# Power_Amp_V3_0.net
KiCad netlist of a schematic drawn in EAGLE
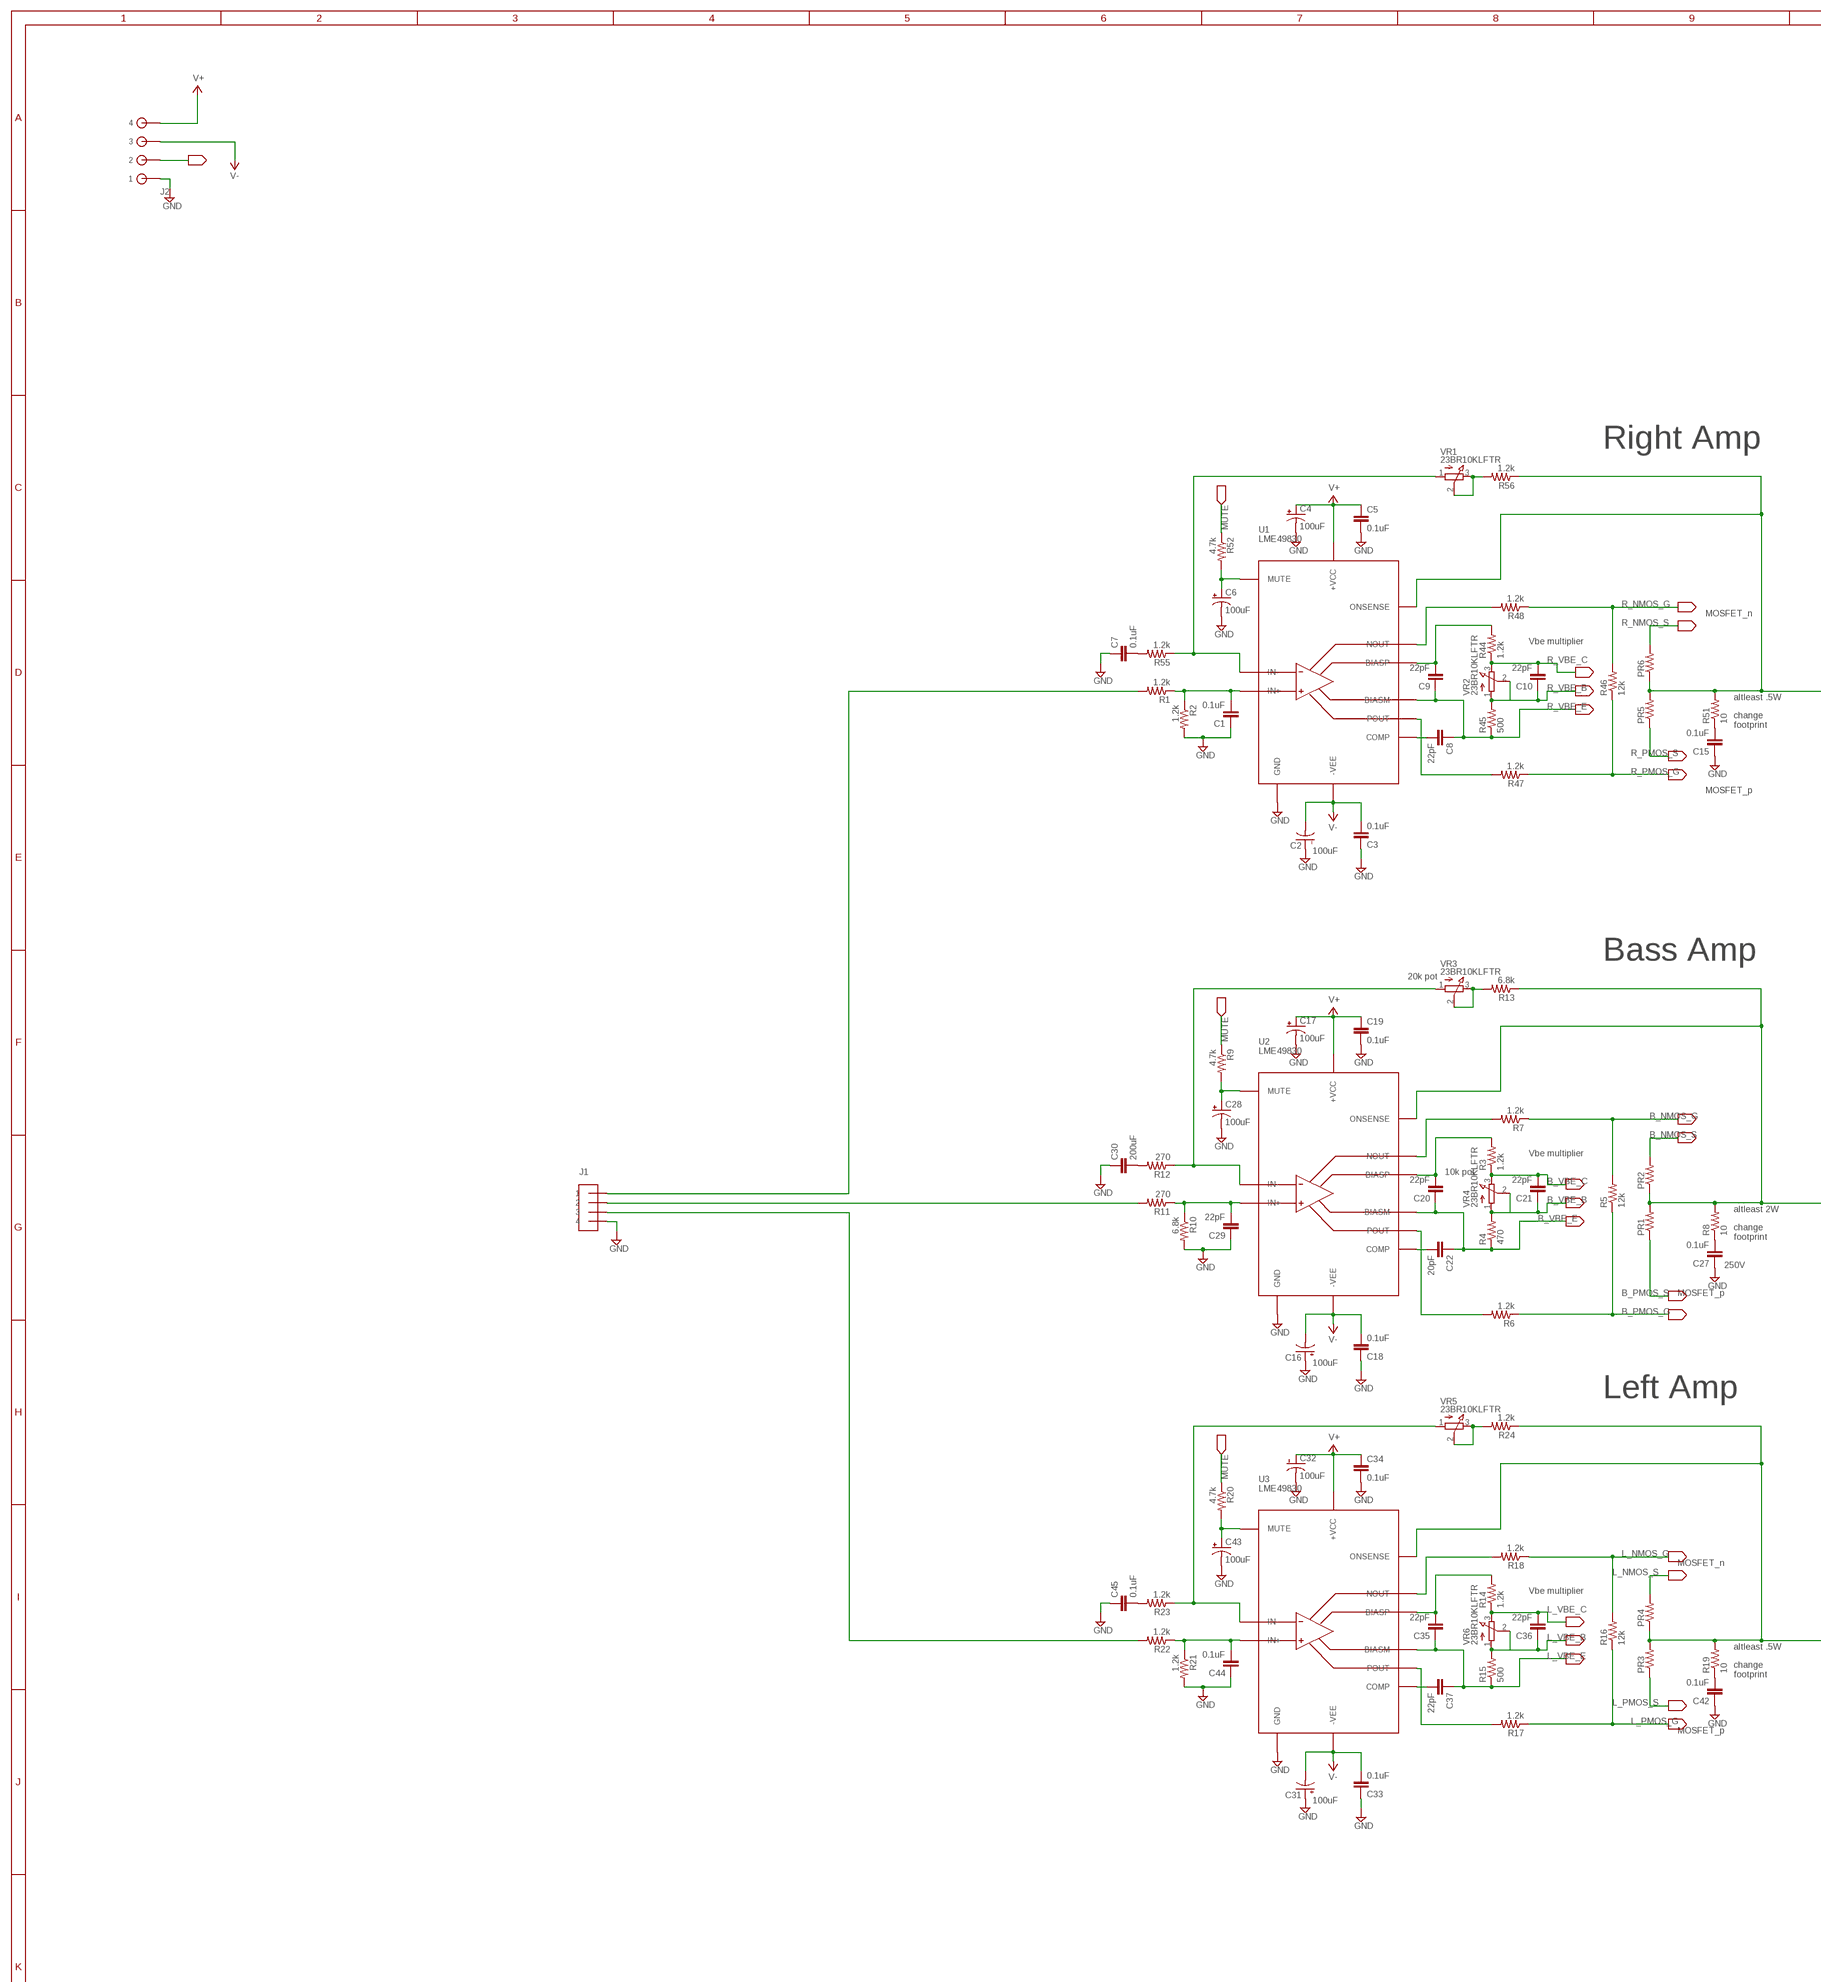
[diagram p0: schematic, sheet 1, part 1 of 3]
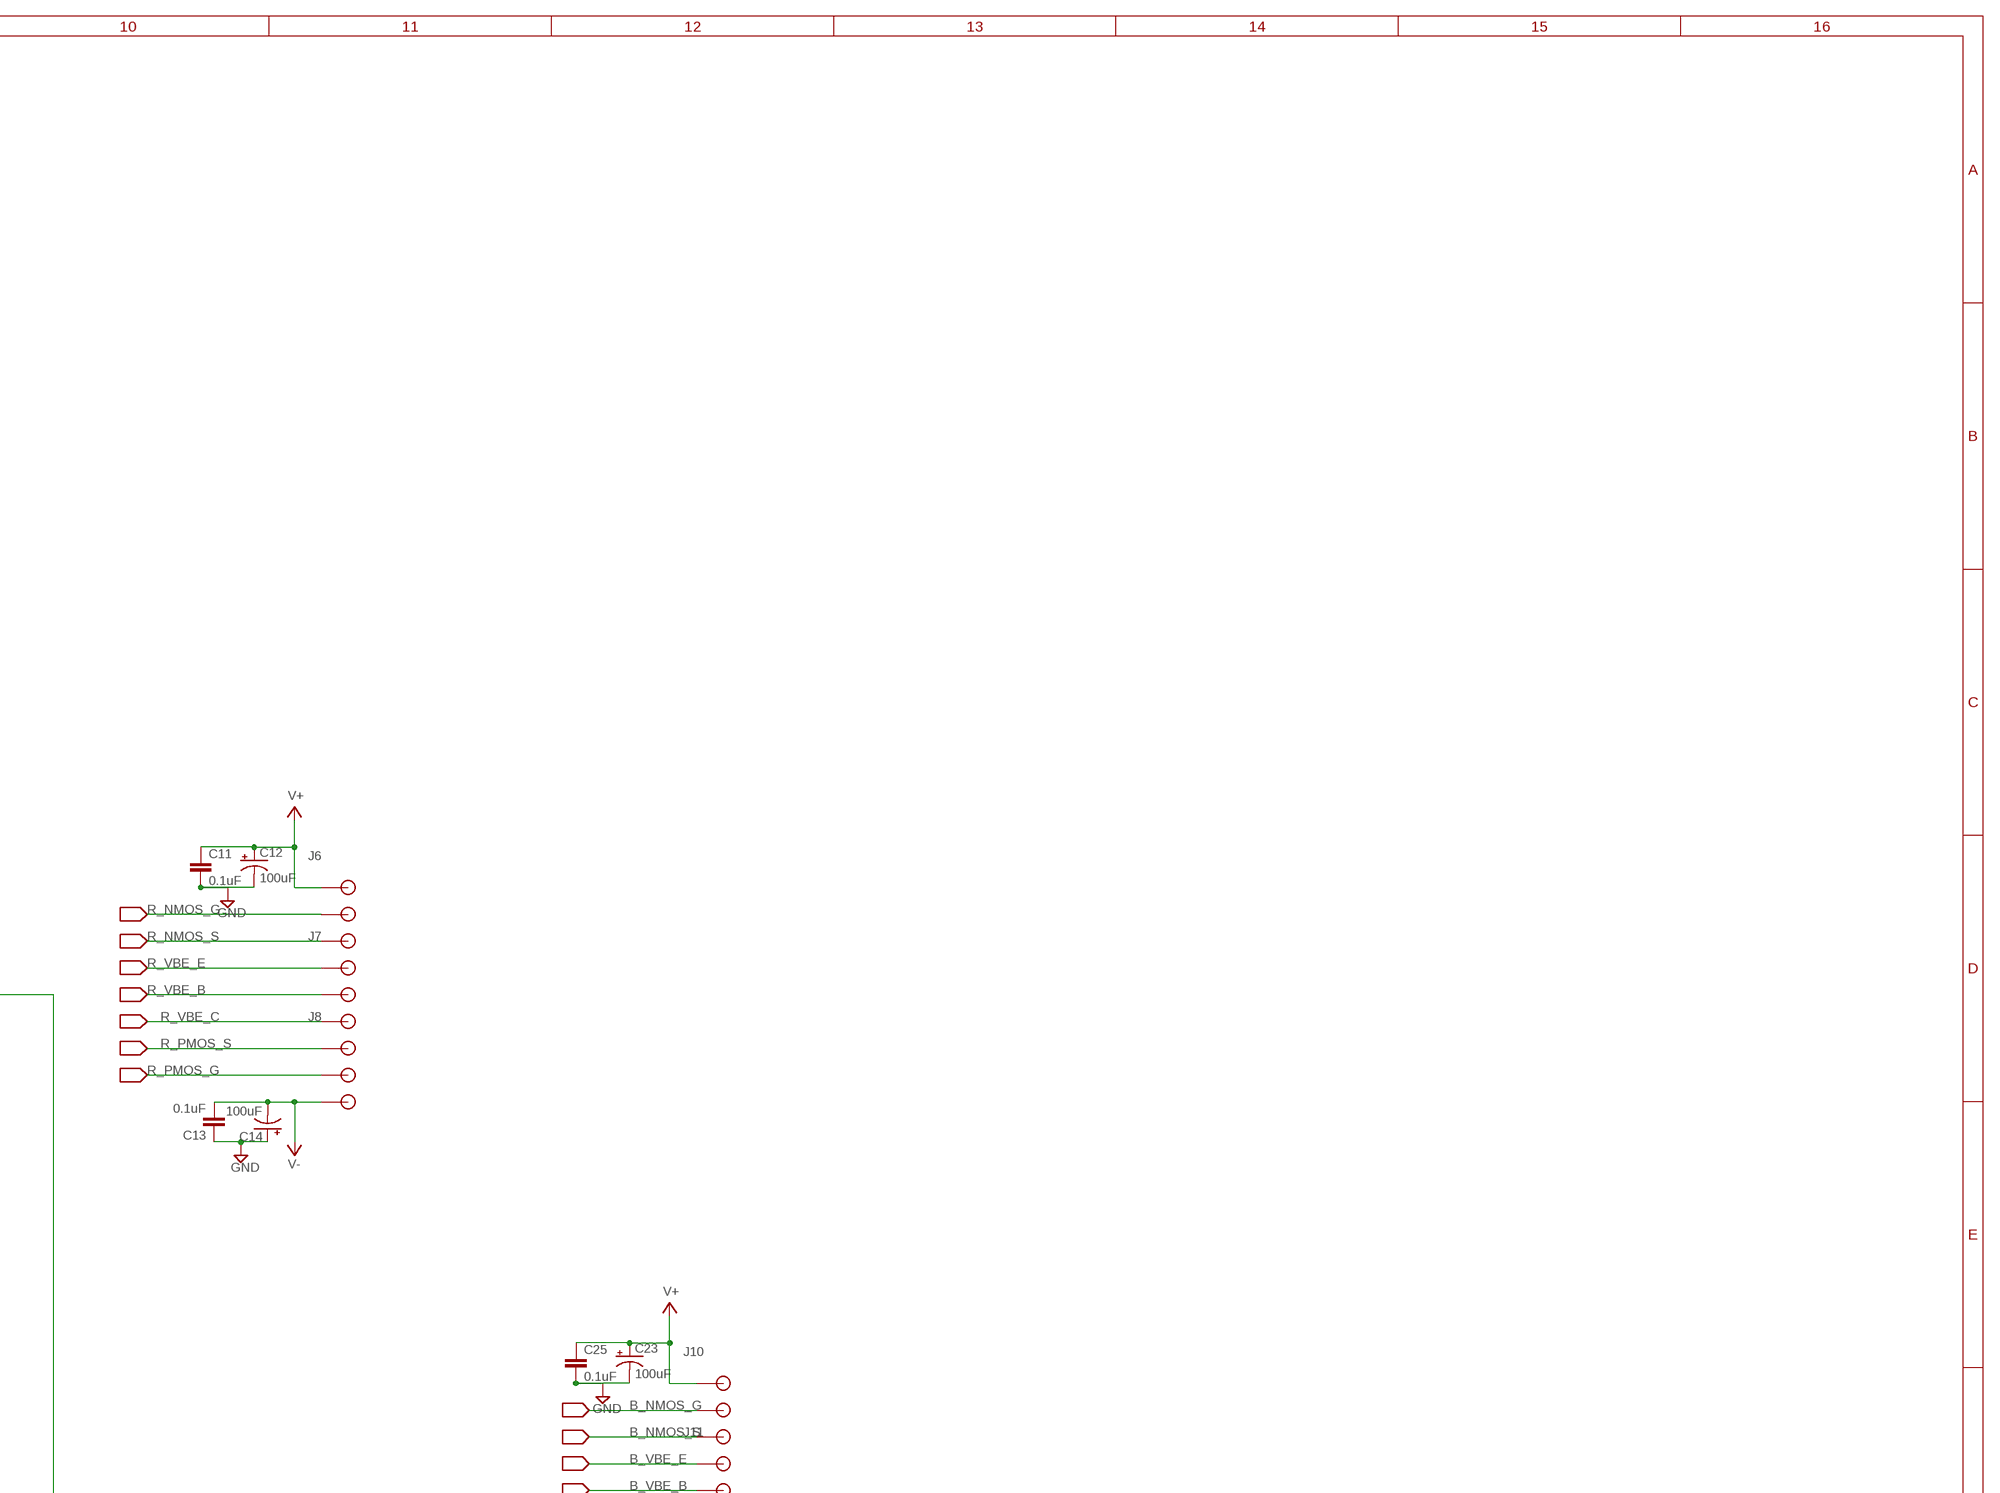
[diagram p1: schematic, sheet 1, part 2 of 3]
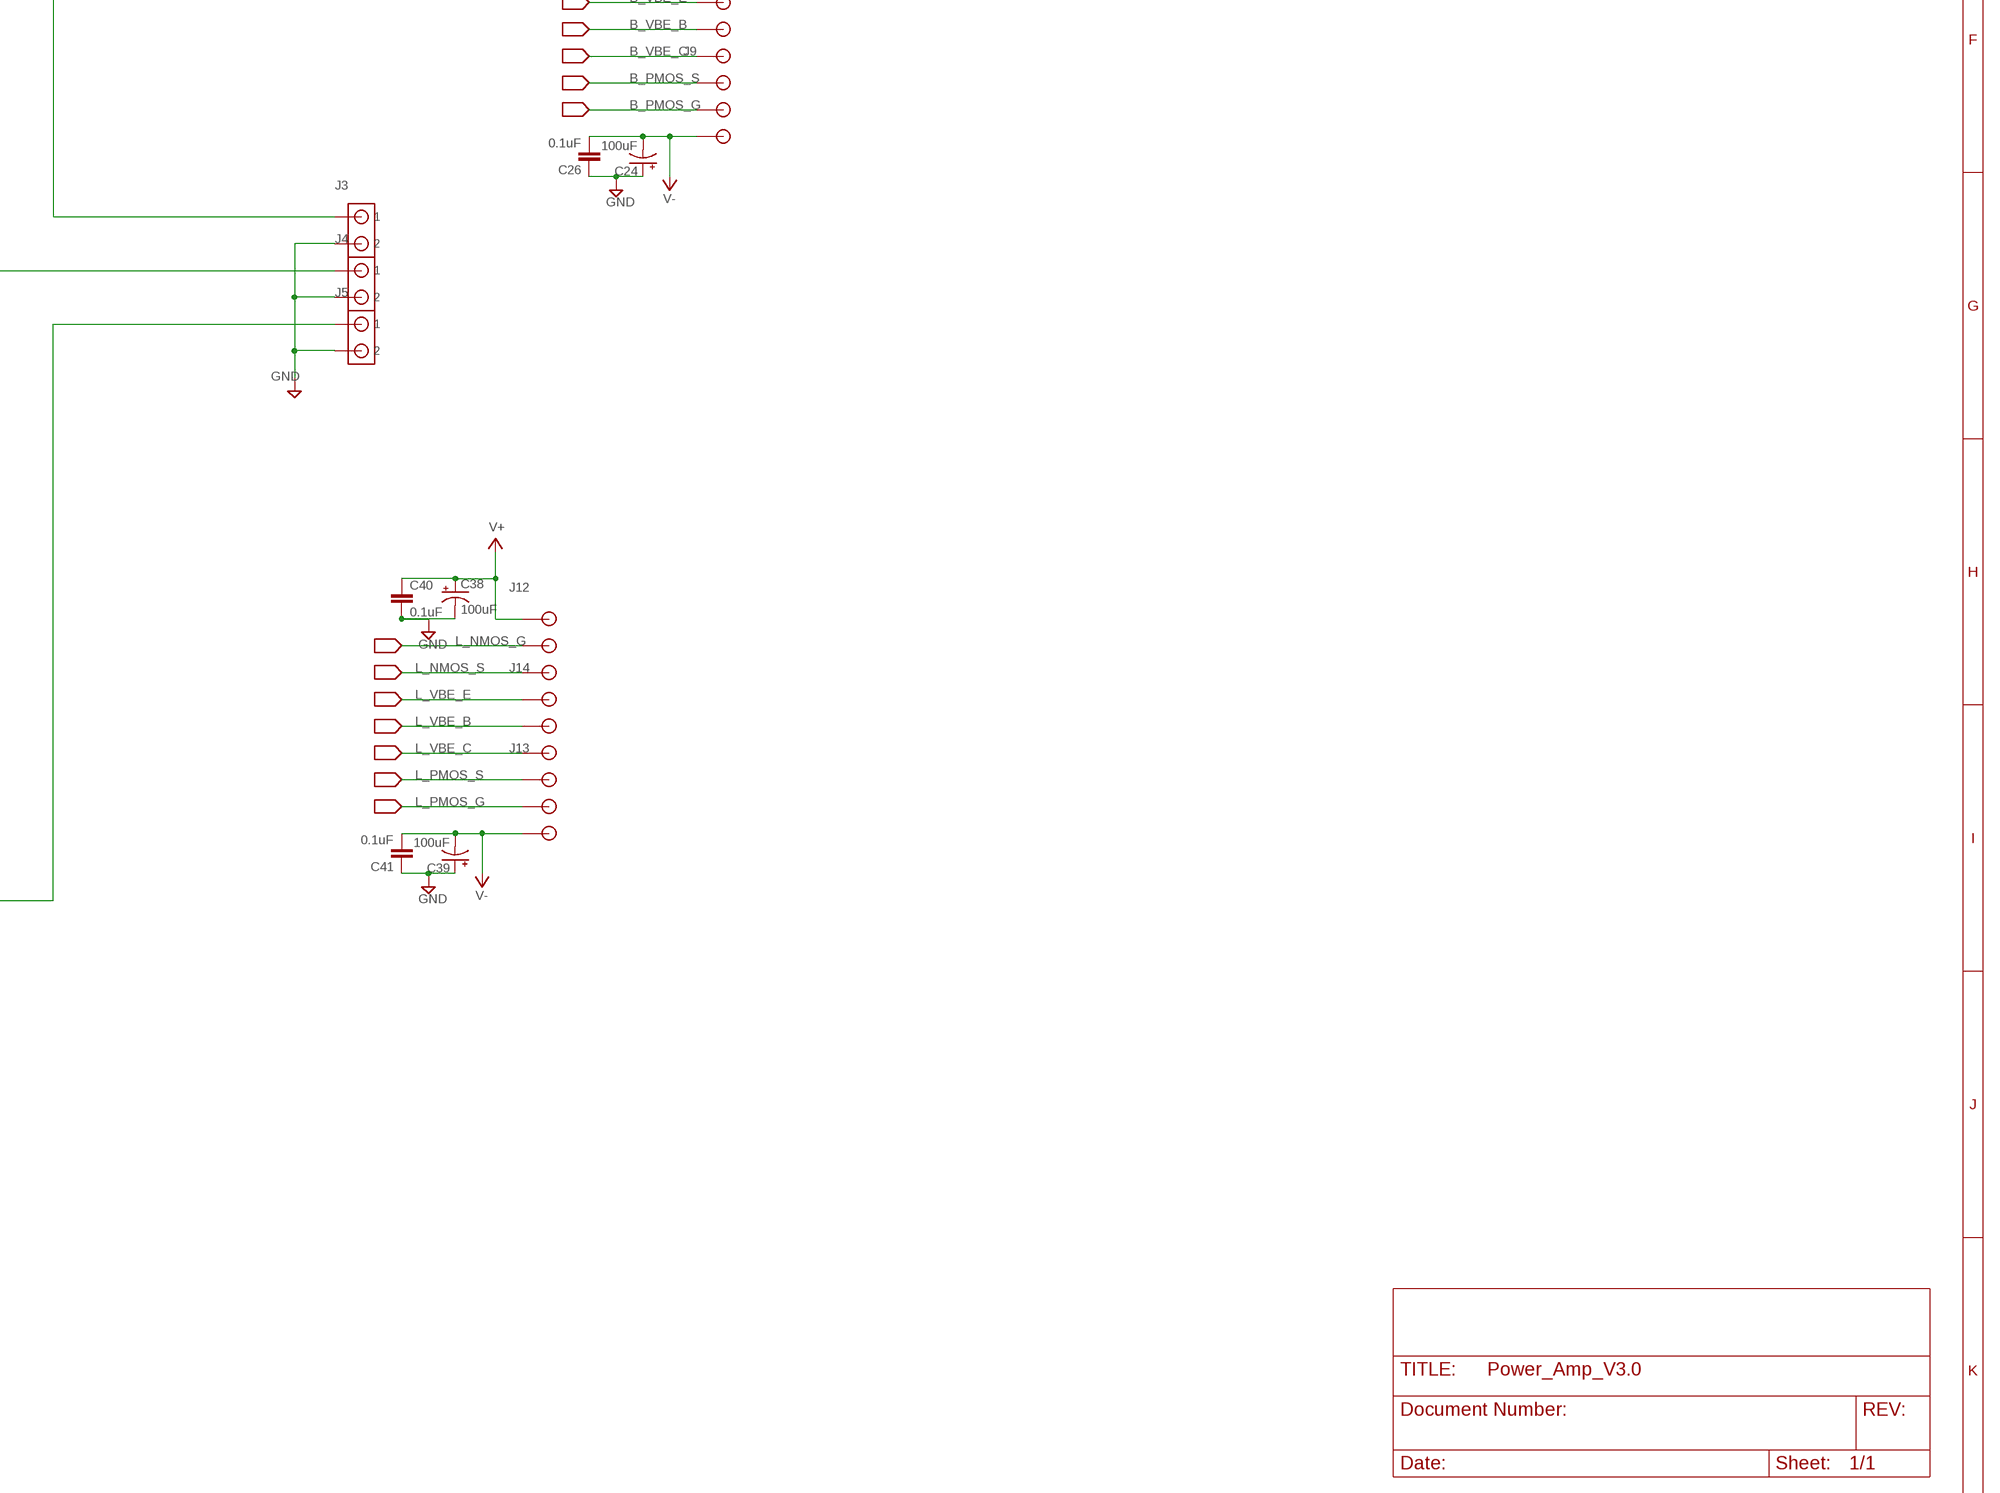
[diagram p2: schematic, sheet 1, part 3 of 3]

(export (version "E")
  (design (tool "Eeschema 10.0.6"))
  (components
    (comp (ref "C1")
      (value "0.1uF")
      (footprint "eagle-import:C050-024X044")
      (libsource (lib "eagle-import") (part "C-EU050-024X044"))
    )
    (comp (ref "C2")
      (value "100uF")
      (footprint "eagle-import:E2,5-6")
      (libsource (lib "eagle-import") (part "CPOL-USE2.5-6"))
    )
    (comp (ref "C3")
      (value "0.1uF")
      (footprint "eagle-import:C050-024X044")
      (libsource (lib "eagle-import") (part "C-EU050-024X044"))
    )
    (comp (ref "C4")
      (value "100uF")
      (footprint "eagle-import:E2,5-6")
      (libsource (lib "eagle-import") (part "CPOL-USE2.5-6"))
    )
    (comp (ref "C5")
      (value "0.1uF")
      (footprint "eagle-import:C050-024X044")
      (libsource (lib "eagle-import") (part "C-EU050-024X044"))
    )
    (comp (ref "C6")
      (value "100uF")
      (footprint "eagle-import:E2,5-6")
      (libsource (lib "eagle-import") (part "CPOL-USE2.5-6"))
    )
    (comp (ref "C7")
      (value "0.1uF")
      (footprint "eagle-import:C050-024X044")
      (libsource (lib "eagle-import") (part "C-EU050-024X044"))
    )
    (comp (ref "C8")
      (value "22pF")
      (footprint "eagle-import:C050-024X044")
      (libsource (lib "eagle-import") (part "C-EU050-024X044"))
    )
    (comp (ref "C9")
      (value "22pF")
      (footprint "eagle-import:C050-024X044")
      (libsource (lib "eagle-import") (part "C-EU050-024X044"))
    )
    (comp (ref "C10")
      (value "22pF")
      (footprint "eagle-import:C050-024X044")
      (libsource (lib "eagle-import") (part "C-EU050-024X044"))
    )
    (comp (ref "C11")
      (value "0.1uF")
      (footprint "eagle-import:C050-024X044")
      (libsource (lib "eagle-import") (part "C-EU050-024X044"))
    )
    (comp (ref "C12")
      (value "100uF")
      (footprint "eagle-import:E2,5-6")
      (libsource (lib "eagle-import") (part "CPOL-USE2.5-6"))
    )
    (comp (ref "C13")
      (value "0.1uF")
      (footprint "eagle-import:C050-024X044")
      (libsource (lib "eagle-import") (part "C-EU050-024X044"))
    )
    (comp (ref "C14")
      (value "100uF")
      (footprint "eagle-import:E2,5-6")
      (libsource (lib "eagle-import") (part "CPOL-USE2.5-6"))
    )
    (comp (ref "C15")
      (value "0.1uF")
      (footprint "eagle-import:C050-024X044")
      (libsource (lib "eagle-import") (part "C-EU050-024X044"))
    )
    (comp (ref "C16")
      (value "100uF")
      (footprint "eagle-import:E2,5-6")
      (libsource (lib "eagle-import") (part "CPOL-USE2.5-6"))
    )
    (comp (ref "C17")
      (value "100uF")
      (footprint "eagle-import:E2,5-6")
      (libsource (lib "eagle-import") (part "CPOL-USE2.5-6"))
    )
    (comp (ref "C18")
      (value "0.1uF")
      (footprint "eagle-import:C050-024X044")
      (libsource (lib "eagle-import") (part "C-EU050-024X044"))
    )
    (comp (ref "C19")
      (value "0.1uF")
      (footprint "eagle-import:C050-024X044")
      (libsource (lib "eagle-import") (part "C-EU050-024X044"))
    )
    (comp (ref "C20")
      (value "22pF")
      (footprint "eagle-import:C050-024X044")
      (libsource (lib "eagle-import") (part "C-EU050-024X044"))
    )
    (comp (ref "C21")
      (value "22pF")
      (footprint "eagle-import:C050-024X044")
      (libsource (lib "eagle-import") (part "C-EU050-024X044"))
    )
    (comp (ref "C22")
      (value "20pF")
      (footprint "eagle-import:C050-024X044")
      (libsource (lib "eagle-import") (part "C-EU050-024X044"))
    )
    (comp (ref "C23")
      (value "100uF")
      (footprint "eagle-import:E2,5-6")
      (libsource (lib "eagle-import") (part "CPOL-USE2.5-6"))
    )
    (comp (ref "C24")
      (value "100uF")
      (footprint "eagle-import:E2,5-6")
      (libsource (lib "eagle-import") (part "CPOL-USE2.5-6"))
    )
    (comp (ref "C25")
      (value "0.1uF")
      (footprint "eagle-import:C050-024X044")
      (libsource (lib "eagle-import") (part "C-EU050-024X044"))
    )
    (comp (ref "C26")
      (value "0.1uF")
      (footprint "eagle-import:C050-024X044")
      (libsource (lib "eagle-import") (part "C-EU050-024X044"))
    )
    (comp (ref "C27")
      (value "0.1uF")
      (footprint "eagle-import:C050-024X044")
      (libsource (lib "eagle-import") (part "C-EU050-024X044"))
    )
    (comp (ref "C28")
      (value "100uF")
      (footprint "eagle-import:E2,5-6")
      (libsource (lib "eagle-import") (part "CPOL-USE2.5-6"))
    )
    (comp (ref "C29")
      (value "22pF")
      (footprint "eagle-import:C050-024X044")
      (libsource (lib "eagle-import") (part "C-EU050-024X044"))
    )
    (comp (ref "C30")
      (value "200uF")
      (footprint "eagle-import:C050-024X044")
      (libsource (lib "eagle-import") (part "C-EU050-024X044"))
    )
    (comp (ref "C31")
      (value "100uF")
      (footprint "eagle-import:E2,5-6")
      (libsource (lib "eagle-import") (part "CPOL-USE2.5-6"))
    )
    (comp (ref "C32")
      (value "100uF")
      (footprint "eagle-import:E2,5-6")
      (libsource (lib "eagle-import") (part "CPOL-USE2.5-6"))
    )
    (comp (ref "C33")
      (value "0.1uF")
      (footprint "eagle-import:C050-024X044")
      (libsource (lib "eagle-import") (part "C-EU050-024X044"))
    )
    (comp (ref "C34")
      (value "0.1uF")
      (footprint "eagle-import:C050-024X044")
      (libsource (lib "eagle-import") (part "C-EU050-024X044"))
    )
    (comp (ref "C35")
      (value "22pF")
      (footprint "eagle-import:C050-024X044")
      (libsource (lib "eagle-import") (part "C-EU050-024X044"))
    )
    (comp (ref "C36")
      (value "22pF")
      (footprint "eagle-import:C050-024X044")
      (libsource (lib "eagle-import") (part "C-EU050-024X044"))
    )
    (comp (ref "C37")
      (value "22pF")
      (footprint "eagle-import:C050-024X044")
      (libsource (lib "eagle-import") (part "C-EU050-024X044"))
    )
    (comp (ref "C38")
      (value "100uF")
      (footprint "eagle-import:E2,5-6")
      (libsource (lib "eagle-import") (part "CPOL-USE2.5-6"))
    )
    (comp (ref "C39")
      (value "100uF")
      (footprint "eagle-import:E2,5-6")
      (libsource (lib "eagle-import") (part "CPOL-USE2.5-6"))
    )
    (comp (ref "C40")
      (value "0.1uF")
      (footprint "eagle-import:C050-024X044")
      (libsource (lib "eagle-import") (part "C-EU050-024X044"))
    )
    (comp (ref "C41")
      (value "0.1uF")
      (footprint "eagle-import:C050-024X044")
      (libsource (lib "eagle-import") (part "C-EU050-024X044"))
    )
    (comp (ref "C42")
      (value "0.1uF")
      (footprint "eagle-import:C050-024X044")
      (libsource (lib "eagle-import") (part "C-EU050-024X044"))
    )
    (comp (ref "C43")
      (value "100uF")
      (footprint "eagle-import:E2,5-6")
      (libsource (lib "eagle-import") (part "CPOL-USE2.5-6"))
    )
    (comp (ref "C44")
      (value "0.1uF")
      (footprint "eagle-import:C050-024X044")
      (libsource (lib "eagle-import") (part "C-EU050-024X044"))
    )
    (comp (ref "C45")
      (value "0.1uF")
      (footprint "eagle-import:C050-024X044")
      (libsource (lib "eagle-import") (part "C-EU050-024X044"))
    )
    (comp (ref "J1")
      (value "4_PIN_AMPCONN")
      (footprint "eagle-import:4_PIN_AMPCON")
      (libsource (lib "eagle-import") (part "4_PIN_AMPCONN"))
    )
    (comp (ref "J2")
      (value "1984633")
      (footprint "eagle-import:1984633")
      (libsource (lib "eagle-import") (part "1984633"))
    )
    (comp (ref "J3")
      (value "2TERMINAL_SPEAKER")
      (footprint "eagle-import:2TERMINAL_SPEAKER")
      (libsource (lib "eagle-import") (part "2TERMINAL_SPEAKER"))
    )
    (comp (ref "J4")
      (value "2TERMINAL_SPEAKER")
      (footprint "eagle-import:2TERMINAL_SPEAKER")
      (libsource (lib "eagle-import") (part "2TERMINAL_SPEAKER"))
    )
    (comp (ref "J5")
      (value "2TERMINAL_SPEAKER")
      (footprint "eagle-import:2TERMINAL_SPEAKER")
      (libsource (lib "eagle-import") (part "2TERMINAL_SPEAKER"))
    )
    (comp (ref "J6")
      (value "OSTVN03A150")
      (footprint "eagle-import:OSTVN03A150")
      (libsource (lib "eagle-import") (part "OSTVN03A150"))
    )
    (comp (ref "J7")
      (value "OSTVN03A150")
      (footprint "eagle-import:OSTVN03A150")
      (libsource (lib "eagle-import") (part "OSTVN03A150"))
    )
    (comp (ref "J8")
      (value "OSTVN03A150")
      (footprint "eagle-import:OSTVN03A150")
      (libsource (lib "eagle-import") (part "OSTVN03A150"))
    )
    (comp (ref "J9")
      (value "OSTVN03A150")
      (footprint "eagle-import:OSTVN03A150")
      (libsource (lib "eagle-import") (part "OSTVN03A150"))
    )
    (comp (ref "J10")
      (value "OSTVN03A150")
      (footprint "eagle-import:OSTVN03A150")
      (libsource (lib "eagle-import") (part "OSTVN03A150"))
    )
    (comp (ref "J11")
      (value "OSTVN03A150")
      (footprint "eagle-import:OSTVN03A150")
      (libsource (lib "eagle-import") (part "OSTVN03A150"))
    )
    (comp (ref "J12")
      (value "OSTVN03A150")
      (footprint "eagle-import:OSTVN03A150")
      (libsource (lib "eagle-import") (part "OSTVN03A150"))
    )
    (comp (ref "J13")
      (value "OSTVN03A150")
      (footprint "eagle-import:OSTVN03A150")
      (libsource (lib "eagle-import") (part "OSTVN03A150"))
    )
    (comp (ref "J14")
      (value "OSTVN03A150")
      (footprint "eagle-import:OSTVN03A150")
      (libsource (lib "eagle-import") (part "OSTVN03A150"))
    )
    (comp (ref "PR1")
      (value "R-US_0617/5V")
      (footprint "eagle-import:0617V")
      (libsource (lib "eagle-import") (part "R-US_0617/5V"))
    )
    (comp (ref "PR2")
      (value "R-US_0617/5V")
      (footprint "eagle-import:0617V")
      (libsource (lib "eagle-import") (part "R-US_0617/5V"))
    )
    (comp (ref "PR3")
      (value "R-US_0617/5V")
      (footprint "eagle-import:0617V")
      (libsource (lib "eagle-import") (part "R-US_0617/5V"))
    )
    (comp (ref "PR4")
      (value "R-US_0617/5V")
      (footprint "eagle-import:0617V")
      (libsource (lib "eagle-import") (part "R-US_0617/5V"))
    )
    (comp (ref "PR5")
      (value "R-US_0617/5V")
      (footprint "eagle-import:0617V")
      (libsource (lib "eagle-import") (part "R-US_0617/5V"))
    )
    (comp (ref "PR6")
      (value "R-US_0617/5V")
      (footprint "eagle-import:0617V")
      (libsource (lib "eagle-import") (part "R-US_0617/5V"))
    )
    (comp (ref "R1")
      (value "1.2k")
      (footprint "eagle-import:0204V")
      (libsource (lib "eagle-import") (part "R-US_0204/2V"))
    )
    (comp (ref "R2")
      (value "1.2k")
      (footprint "eagle-import:0204V")
      (libsource (lib "eagle-import") (part "R-US_0204/2V"))
    )
    (comp (ref "R3")
      (value "1.2k")
      (footprint "eagle-import:0204V")
      (libsource (lib "eagle-import") (part "R-US_0204/2V"))
    )
    (comp (ref "R4")
      (value "470")
      (footprint "eagle-import:0204V")
      (libsource (lib "eagle-import") (part "R-US_0204/2V"))
    )
    (comp (ref "R5")
      (value "12k")
      (footprint "eagle-import:0204V")
      (libsource (lib "eagle-import") (part "R-US_0204/2V"))
    )
    (comp (ref "R6")
      (value "1.2k")
      (footprint "eagle-import:0204V")
      (libsource (lib "eagle-import") (part "R-US_0204/2V"))
    )
    (comp (ref "R7")
      (value "1.2k")
      (footprint "eagle-import:0204V")
      (libsource (lib "eagle-import") (part "R-US_0204/2V"))
    )
    (comp (ref "R8")
      (value "10")
      (footprint "eagle-import:0309V")
      (libsource (lib "eagle-import") (part "R-US_0309/V"))
    )
    (comp (ref "R9")
      (value "4.7k")
      (footprint "eagle-import:0204V")
      (libsource (lib "eagle-import") (part "R-US_0204/2V"))
    )
    (comp (ref "R10")
      (value "6.8k")
      (footprint "eagle-import:0204V")
      (libsource (lib "eagle-import") (part "R-US_0204/2V"))
    )
    (comp (ref "R11")
      (value "270")
      (footprint "eagle-import:0204V")
      (libsource (lib "eagle-import") (part "R-US_0204/2V"))
    )
    (comp (ref "R12")
      (value "270")
      (footprint "eagle-import:0204V")
      (libsource (lib "eagle-import") (part "R-US_0204/2V"))
    )
    (comp (ref "R13")
      (value "6.8k")
      (footprint "eagle-import:0204V")
      (libsource (lib "eagle-import") (part "R-US_0204/2V"))
    )
    (comp (ref "R14")
      (value "1.2k")
      (footprint "eagle-import:0204V")
      (libsource (lib "eagle-import") (part "R-US_0204/2V"))
    )
    (comp (ref "R15")
      (value "500")
      (footprint "eagle-import:0204V")
      (libsource (lib "eagle-import") (part "R-US_0204/2V"))
    )
    (comp (ref "R16")
      (value "12k")
      (footprint "eagle-import:0204V")
      (libsource (lib "eagle-import") (part "R-US_0204/2V"))
    )
    (comp (ref "R17")
      (value "1.2k")
      (footprint "eagle-import:0204V")
      (libsource (lib "eagle-import") (part "R-US_0204/2V"))
    )
    (comp (ref "R18")
      (value "1.2k")
      (footprint "eagle-import:0204V")
      (libsource (lib "eagle-import") (part "R-US_0204/2V"))
    )
    (comp (ref "R19")
      (value "10")
      (footprint "eagle-import:0309V")
      (libsource (lib "eagle-import") (part "R-US_0309/V"))
    )
    (comp (ref "R20")
      (value "4.7k")
      (footprint "eagle-import:0204V")
      (libsource (lib "eagle-import") (part "R-US_0204/2V"))
    )
    (comp (ref "R21")
      (value "1.2k")
      (footprint "eagle-import:0204V")
      (libsource (lib "eagle-import") (part "R-US_0204/2V"))
    )
    (comp (ref "R22")
      (value "1.2k")
      (footprint "eagle-import:0204V")
      (libsource (lib "eagle-import") (part "R-US_0204/2V"))
    )
    (comp (ref "R23")
      (value "1.2k")
      (footprint "eagle-import:0204V")
      (libsource (lib "eagle-import") (part "R-US_0204/2V"))
    )
    (comp (ref "R24")
      (value "1.2k")
      (footprint "eagle-import:0204V")
      (libsource (lib "eagle-import") (part "R-US_0204/2V"))
    )
    (comp (ref "R44")
      (value "1.2k")
      (footprint "eagle-import:0204V")
      (libsource (lib "eagle-import") (part "R-US_0204/2V"))
    )
    (comp (ref "R45")
      (value "500")
      (footprint "eagle-import:0204V")
      (libsource (lib "eagle-import") (part "R-US_0204/2V"))
    )
    (comp (ref "R46")
      (value "12k")
      (footprint "eagle-import:0204V")
      (libsource (lib "eagle-import") (part "R-US_0204/2V"))
    )
    (comp (ref "R47")
      (value "1.2k")
      (footprint "eagle-import:0204V")
      (libsource (lib "eagle-import") (part "R-US_0204/2V"))
    )
    (comp (ref "R48")
      (value "1.2k")
      (footprint "eagle-import:0204V")
      (libsource (lib "eagle-import") (part "R-US_0204/2V"))
    )
    (comp (ref "R51")
      (value "10")
      (footprint "eagle-import:0309V")
      (libsource (lib "eagle-import") (part "R-US_0309/V"))
    )
    (comp (ref "R52")
      (value "4.7k")
      (footprint "eagle-import:0204V")
      (libsource (lib "eagle-import") (part "R-US_0204/2V"))
    )
    (comp (ref "R55")
      (value "1.2k")
      (footprint "eagle-import:0204V")
      (libsource (lib "eagle-import") (part "R-US_0204/2V"))
    )
    (comp (ref "R56")
      (value "1.2k")
      (footprint "eagle-import:0204V")
      (libsource (lib "eagle-import") (part "R-US_0204/2V"))
    )
    (comp (ref "U1")
      (value "LME49830")
      (footprint "eagle-import:NDN0015A")
      (libsource (lib "eagle-import") (part "LME49830"))
    )
    (comp (ref "U2")
      (value "LME49830")
      (footprint "eagle-import:NDN0015A")
      (libsource (lib "eagle-import") (part "LME49830"))
    )
    (comp (ref "U3")
      (value "LME49830")
      (footprint "eagle-import:NDN0015A")
      (libsource (lib "eagle-import") (part "LME49830"))
    )
    (comp (ref "VR1")
      (value "23BR10KLFTR")
      (footprint "eagle-import:23BR10KLFTR")
      (libsource (lib "eagle-import") (part "23BR10KLFTR"))
    )
    (comp (ref "VR2")
      (value "23BR10KLFTR")
      (footprint "eagle-import:23BR10KLFTR")
      (libsource (lib "eagle-import") (part "23BR10KLFTR"))
    )
    (comp (ref "VR3")
      (value "23BR10KLFTR")
      (footprint "eagle-import:23BR10KLFTR")
      (libsource (lib "eagle-import") (part "23BR10KLFTR"))
    )
    (comp (ref "VR4")
      (value "23BR10KLFTR")
      (footprint "eagle-import:23BR10KLFTR")
      (libsource (lib "eagle-import") (part "23BR10KLFTR"))
    )
    (comp (ref "VR5")
      (value "23BR10KLFTR")
      (footprint "eagle-import:23BR10KLFTR")
      (libsource (lib "eagle-import") (part "23BR10KLFTR"))
    )
    (comp (ref "VR6")
      (value "23BR10KLFTR")
      (footprint "eagle-import:23BR10KLFTR")
      (libsource (lib "eagle-import") (part "23BR10KLFTR"))
    )
  )
  (nets
    (net (code "1") (name "/B_NMOS_G") (class "Default")
      (node (ref "J10") (pin "P$2") (pinfunction "2_P$2") (pintype "bidirectional"))
      (node (ref "R5") (pin "2") (pinfunction "2_2") (pintype "passive"))
      (node (ref "R7") (pin "1") (pinfunction "1_1") (pintype "passive"))
    )
    (net (code "2") (name "/B_NMOS_S") (class "Default")
      (node (ref "J10") (pin "P$3") (pinfunction "3_P$3") (pintype "bidirectional"))
      (node (ref "PR2") (pin "2") (pinfunction "2_2") (pintype "passive"))
    )
    (net (code "3") (name "/B_PMOS_G") (class "Default")
      (node (ref "J9") (pin "P$2") (pinfunction "2_P$2") (pintype "bidirectional"))
      (node (ref "R5") (pin "1") (pinfunction "1_1") (pintype "passive"))
      (node (ref "R6") (pin "1") (pinfunction "1_1") (pintype "passive"))
    )
    (net (code "4") (name "/B_PMOS_S") (class "Default")
      (node (ref "J9") (pin "P$1") (pinfunction "1_P$1") (pintype "bidirectional"))
      (node (ref "PR1") (pin "1") (pinfunction "1_1") (pintype "passive"))
    )
    (net (code "5") (name "/B_VBE_B") (class "Default")
      (node (ref "C21") (pin "1") (pinfunction "1_1") (pintype "passive"))
      (node (ref "J11") (pin "P$2") (pinfunction "2_P$2") (pintype "bidirectional"))
      (node (ref "R4") (pin "2") (pinfunction "2_2") (pintype "passive"))
      (node (ref "VR4") (pin "1") (pinfunction "A_1") (pintype "passive"))
      (node (ref "VR4") (pin "2") (pinfunction "B_2") (pintype "passive"))
    )
    (net (code "6") (name "/B_VBE_C") (class "Default")
      (node (ref "C21") (pin "2") (pinfunction "2_2") (pintype "passive"))
      (node (ref "J11") (pin "P$3") (pinfunction "3_P$3") (pintype "bidirectional"))
      (node (ref "R3") (pin "1") (pinfunction "1_1") (pintype "passive"))
      (node (ref "VR4") (pin "3") (pinfunction "C_3") (pintype "passive"))
    )
    (net (code "7") (name "/B_VBE_E") (class "Default")
      (node (ref "C20") (pin "1") (pinfunction "1_1") (pintype "passive"))
      (node (ref "C22") (pin "1") (pinfunction "1_1") (pintype "passive"))
      (node (ref "J11") (pin "P$1") (pinfunction "1_P$1") (pintype "bidirectional"))
      (node (ref "R4") (pin "1") (pinfunction "1_1") (pintype "passive"))
      (node (ref "U2") (pin "P11") (pinfunction "BIASM_P11") (pintype "bidirectional"))
    )
    (net (code "8") (name "/L_NMOS_G") (class "Default")
      (node (ref "J12") (pin "P$2") (pinfunction "2_P$2") (pintype "bidirectional"))
      (node (ref "R16") (pin "2") (pinfunction "2_2") (pintype "passive"))
      (node (ref "R18") (pin "1") (pinfunction "1_1") (pintype "passive"))
    )
    (net (code "9") (name "/L_NMOS_S") (class "Default")
      (node (ref "J12") (pin "P$3") (pinfunction "3_P$3") (pintype "bidirectional"))
      (node (ref "PR4") (pin "2") (pinfunction "2_2") (pintype "passive"))
    )
    (net (code "10") (name "/L_PMOS_G") (class "Default")
      (node (ref "J13") (pin "P$2") (pinfunction "2_P$2") (pintype "bidirectional"))
      (node (ref "R16") (pin "1") (pinfunction "1_1") (pintype "passive"))
      (node (ref "R17") (pin "1") (pinfunction "1_1") (pintype "passive"))
    )
    (net (code "11") (name "/L_PMOS_S") (class "Default")
      (node (ref "J13") (pin "P$1") (pinfunction "1_P$1") (pintype "bidirectional"))
      (node (ref "PR3") (pin "1") (pinfunction "1_1") (pintype "passive"))
    )
    (net (code "12") (name "/L_VBE_B") (class "Default")
      (node (ref "C36") (pin "1") (pinfunction "1_1") (pintype "passive"))
      (node (ref "J14") (pin "P$2") (pinfunction "2_P$2") (pintype "bidirectional"))
      (node (ref "R15") (pin "2") (pinfunction "2_2") (pintype "passive"))
      (node (ref "VR6") (pin "1") (pinfunction "A_1") (pintype "passive"))
      (node (ref "VR6") (pin "2") (pinfunction "B_2") (pintype "passive"))
    )
    (net (code "13") (name "/L_VBE_C") (class "Default")
      (node (ref "C36") (pin "2") (pinfunction "2_2") (pintype "passive"))
      (node (ref "J14") (pin "P$3") (pinfunction "3_P$3") (pintype "bidirectional"))
      (node (ref "R14") (pin "1") (pinfunction "1_1") (pintype "passive"))
      (node (ref "VR6") (pin "3") (pinfunction "C_3") (pintype "passive"))
    )
    (net (code "14") (name "/L_VBE_E") (class "Default")
      (node (ref "C35") (pin "1") (pinfunction "1_1") (pintype "passive"))
      (node (ref "C37") (pin "1") (pinfunction "1_1") (pintype "passive"))
      (node (ref "J14") (pin "P$1") (pinfunction "1_P$1") (pintype "bidirectional"))
      (node (ref "R15") (pin "1") (pinfunction "1_1") (pintype "passive"))
      (node (ref "U3") (pin "P11") (pinfunction "BIASM_P11") (pintype "bidirectional"))
    )
    (net (code "15") (name "/MUTE") (class "Default")
      (node (ref "J2") (pin "P$2") (pinfunction "2_P$2") (pintype "passive"))
      (node (ref "R20") (pin "1") (pinfunction "1_1") (pintype "passive"))
      (node (ref "R52") (pin "1") (pinfunction "1_1") (pintype "passive"))
      (node (ref "R9") (pin "1") (pinfunction "1_1") (pintype "passive"))
    )
    (net (code "16") (name "/R_NMOS_G") (class "Default")
      (node (ref "J6") (pin "P$2") (pinfunction "2_P$2") (pintype "bidirectional"))
      (node (ref "R46") (pin "2") (pinfunction "2_2") (pintype "passive"))
      (node (ref "R48") (pin "1") (pinfunction "1_1") (pintype "passive"))
    )
    (net (code "17") (name "/R_NMOS_S") (class "Default")
      (node (ref "J6") (pin "P$3") (pinfunction "3_P$3") (pintype "bidirectional"))
      (node (ref "PR6") (pin "2") (pinfunction "2_2") (pintype "passive"))
    )
    (net (code "18") (name "/R_PMOS_G") (class "Default")
      (node (ref "J8") (pin "P$2") (pinfunction "2_P$2") (pintype "bidirectional"))
      (node (ref "R46") (pin "1") (pinfunction "1_1") (pintype "passive"))
      (node (ref "R47") (pin "1") (pinfunction "1_1") (pintype "passive"))
    )
    (net (code "19") (name "/R_PMOS_S") (class "Default")
      (node (ref "J8") (pin "P$1") (pinfunction "1_P$1") (pintype "bidirectional"))
      (node (ref "PR5") (pin "1") (pinfunction "1_1") (pintype "passive"))
    )
    (net (code "20") (name "/R_VBE_B") (class "Default")
      (node (ref "C10") (pin "1") (pinfunction "1_1") (pintype "passive"))
      (node (ref "J7") (pin "P$2") (pinfunction "2_P$2") (pintype "bidirectional"))
      (node (ref "R45") (pin "2") (pinfunction "2_2") (pintype "passive"))
      (node (ref "VR2") (pin "1") (pinfunction "A_1") (pintype "passive"))
      (node (ref "VR2") (pin "2") (pinfunction "B_2") (pintype "passive"))
    )
    (net (code "21") (name "/R_VBE_C") (class "Default")
      (node (ref "C10") (pin "2") (pinfunction "2_2") (pintype "passive"))
      (node (ref "J7") (pin "P$3") (pinfunction "3_P$3") (pintype "bidirectional"))
      (node (ref "R44") (pin "1") (pinfunction "1_1") (pintype "passive"))
      (node (ref "VR2") (pin "3") (pinfunction "C_3") (pintype "passive"))
    )
    (net (code "22") (name "/R_VBE_E") (class "Default")
      (node (ref "C8") (pin "1") (pinfunction "1_1") (pintype "passive"))
      (node (ref "C9") (pin "1") (pinfunction "1_1") (pintype "passive"))
      (node (ref "J7") (pin "P$1") (pinfunction "1_P$1") (pintype "bidirectional"))
      (node (ref "R45") (pin "1") (pinfunction "1_1") (pintype "passive"))
      (node (ref "U1") (pin "P11") (pinfunction "BIASM_P11") (pintype "bidirectional"))
    )
    (net (code "23") (name "GND") (class "Default")
      (node (ref "C1") (pin "1") (pinfunction "1_1") (pintype "passive"))
      (node (ref "C11") (pin "2") (pinfunction "2_2") (pintype "passive"))
      (node (ref "C12") (pin "-") (pinfunction "-_-") (pintype "passive"))
      (node (ref "C13") (pin "1") (pinfunction "1_1") (pintype "passive"))
      (node (ref "C14") (pin "+") (pinfunction "+_+") (pintype "passive"))
      (node (ref "C15") (pin "1") (pinfunction "1_1") (pintype "passive"))
      (node (ref "C16") (pin "+") (pinfunction "+_+") (pintype "passive"))
      (node (ref "C17") (pin "-") (pinfunction "-_-") (pintype "passive"))
      (node (ref "C18") (pin "1") (pinfunction "1_1") (pintype "passive"))
      (node (ref "C19") (pin "2") (pinfunction "2_2") (pintype "passive"))
      (node (ref "C2") (pin "+") (pinfunction "+_+") (pintype "passive"))
      (node (ref "C23") (pin "-") (pinfunction "-_-") (pintype "passive"))
      (node (ref "C24") (pin "+") (pinfunction "+_+") (pintype "passive"))
      (node (ref "C25") (pin "2") (pinfunction "2_2") (pintype "passive"))
      (node (ref "C26") (pin "1") (pinfunction "1_1") (pintype "passive"))
      (node (ref "C27") (pin "1") (pinfunction "1_1") (pintype "passive"))
      (node (ref "C28") (pin "-") (pinfunction "-_-") (pintype "passive"))
      (node (ref "C29") (pin "1") (pinfunction "1_1") (pintype "passive"))
      (node (ref "C3") (pin "1") (pinfunction "1_1") (pintype "passive"))
      (node (ref "C30") (pin "1") (pinfunction "1_1") (pintype "passive"))
      (node (ref "C31") (pin "+") (pinfunction "+_+") (pintype "passive"))
      (node (ref "C32") (pin "-") (pinfunction "-_-") (pintype "passive"))
      (node (ref "C33") (pin "1") (pinfunction "1_1") (pintype "passive"))
      (node (ref "C34") (pin "2") (pinfunction "2_2") (pintype "passive"))
      (node (ref "C38") (pin "-") (pinfunction "-_-") (pintype "passive"))
      (node (ref "C39") (pin "+") (pinfunction "+_+") (pintype "passive"))
      (node (ref "C4") (pin "-") (pinfunction "-_-") (pintype "passive"))
      (node (ref "C40") (pin "2") (pinfunction "2_2") (pintype "passive"))
      (node (ref "C41") (pin "1") (pinfunction "1_1") (pintype "passive"))
      (node (ref "C42") (pin "1") (pinfunction "1_1") (pintype "passive"))
      (node (ref "C43") (pin "-") (pinfunction "-_-") (pintype "passive"))
      (node (ref "C44") (pin "1") (pinfunction "1_1") (pintype "passive"))
      (node (ref "C45") (pin "1") (pinfunction "1_1") (pintype "passive"))
      (node (ref "C5") (pin "2") (pinfunction "2_2") (pintype "passive"))
      (node (ref "C6") (pin "-") (pinfunction "-_-") (pintype "passive"))
      (node (ref "C7") (pin "1") (pinfunction "1_1") (pintype "passive"))
      (node (ref "J1") (pin "4") (pinfunction "4_4") (pintype "passive"))
      (node (ref "J2") (pin "P$1") (pinfunction "1_P$1") (pintype "passive"))
      (node (ref "J3") (pin "P$2") (pinfunction "2_P$2") (pintype "passive"))
      (node (ref "J4") (pin "P$2") (pinfunction "2_P$2") (pintype "passive"))
      (node (ref "J5") (pin "P$2") (pinfunction "2_P$2") (pintype "passive"))
      (node (ref "R10") (pin "2") (pinfunction "2_2") (pintype "passive"))
      (node (ref "R2") (pin "2") (pinfunction "2_2") (pintype "passive"))
      (node (ref "R21") (pin "2") (pinfunction "2_2") (pintype "passive"))
      (node (ref "U1") (pin "P3") (pinfunction "GND_P3") (pintype "bidirectional"))
      (node (ref "U2") (pin "P3") (pinfunction "GND_P3") (pintype "bidirectional"))
      (node (ref "U3") (pin "P3") (pinfunction "GND_P3") (pintype "bidirectional"))
    )
    (net (code "24") (name "Net-(C7-Pad2)") (class "Default")
      (node (ref "C7") (pin "2") (pinfunction "2_2") (pintype "passive"))
      (node (ref "R55") (pin "2") (pinfunction "2_2") (pintype "passive"))
    )
    (net (code "25") (name "Net-(C15-Pad2)") (class "Default")
      (node (ref "C15") (pin "2") (pinfunction "2_2") (pintype "passive"))
      (node (ref "R51") (pin "1") (pinfunction "1_1") (pintype "passive"))
    )
    (net (code "26") (name "Net-(C27-Pad2)") (class "Default")
      (node (ref "C27") (pin "2") (pinfunction "2_2") (pintype "passive"))
      (node (ref "R8") (pin "1") (pinfunction "1_1") (pintype "passive"))
    )
    (net (code "27") (name "Net-(C30-Pad2)") (class "Default")
      (node (ref "C30") (pin "2") (pinfunction "2_2") (pintype "passive"))
      (node (ref "R12") (pin "2") (pinfunction "2_2") (pintype "passive"))
    )
    (net (code "28") (name "Net-(C42-Pad2)") (class "Default")
      (node (ref "C42") (pin "2") (pinfunction "2_2") (pintype "passive"))
      (node (ref "R19") (pin "1") (pinfunction "1_1") (pintype "passive"))
    )
    (net (code "29") (name "Net-(C45-Pad2)") (class "Default")
      (node (ref "C45") (pin "2") (pinfunction "2_2") (pintype "passive"))
      (node (ref "R23") (pin "2") (pinfunction "2_2") (pintype "passive"))
    )
    (net (code "30") (name "Net-(J1-Pad1)") (class "Default")
      (node (ref "J1") (pin "1") (pinfunction "1_1") (pintype "passive"))
      (node (ref "R1") (pin "2") (pinfunction "2_2") (pintype "passive"))
    )
    (net (code "31") (name "Net-(J1-Pad2)") (class "Default")
      (node (ref "J1") (pin "2") (pinfunction "2_2") (pintype "passive"))
      (node (ref "R11") (pin "2") (pinfunction "2_2") (pintype "passive"))
    )
    (net (code "32") (name "Net-(J1-Pad3)") (class "Default")
      (node (ref "J1") (pin "3") (pinfunction "3_3") (pintype "passive"))
      (node (ref "R22") (pin "2") (pinfunction "2_2") (pintype "passive"))
    )
    (net (code "33") (name "Net-(J3-1)") (class "Default")
      (node (ref "J3") (pin "P$1") (pinfunction "1_P$1") (pintype "passive"))
      (node (ref "PR5") (pin "2") (pinfunction "2_2") (pintype "passive"))
      (node (ref "PR6") (pin "1") (pinfunction "1_1") (pintype "passive"))
      (node (ref "R51") (pin "2") (pinfunction "2_2") (pintype "passive"))
      (node (ref "R56") (pin "1") (pinfunction "1_1") (pintype "passive"))
      (node (ref "U1") (pin "P$8") (pinfunction "ONSENSE_P$8") (pintype "bidirectional"))
    )
    (net (code "34") (name "Net-(J4-1)") (class "Default")
      (node (ref "J4") (pin "P$1") (pinfunction "1_P$1") (pintype "passive"))
      (node (ref "PR1") (pin "2") (pinfunction "2_2") (pintype "passive"))
      (node (ref "PR2") (pin "1") (pinfunction "1_1") (pintype "passive"))
      (node (ref "R13") (pin "1") (pinfunction "1_1") (pintype "passive"))
      (node (ref "R8") (pin "2") (pinfunction "2_2") (pintype "passive"))
      (node (ref "U2") (pin "P$8") (pinfunction "ONSENSE_P$8") (pintype "bidirectional"))
    )
    (net (code "35") (name "Net-(J5-1)") (class "Default")
      (node (ref "J5") (pin "P$1") (pinfunction "1_P$1") (pintype "passive"))
      (node (ref "PR3") (pin "2") (pinfunction "2_2") (pintype "passive"))
      (node (ref "PR4") (pin "1") (pinfunction "1_1") (pintype "passive"))
      (node (ref "R19") (pin "2") (pinfunction "2_2") (pintype "passive"))
      (node (ref "R24") (pin "1") (pinfunction "1_1") (pintype "passive"))
      (node (ref "U3") (pin "P$8") (pinfunction "ONSENSE_P$8") (pintype "bidirectional"))
    )
    (net (code "36") (name "Net-(U1-BIASP)") (class "Default")
      (node (ref "C9") (pin "2") (pinfunction "2_2") (pintype "passive"))
      (node (ref "R44") (pin "2") (pinfunction "2_2") (pintype "passive"))
      (node (ref "U1") (pin "P12") (pinfunction "BIASP_P12") (pintype "bidirectional"))
    )
    (net (code "37") (name "Net-(U1-COMP)") (class "Default")
      (node (ref "C8") (pin "2") (pinfunction "2_2") (pintype "passive"))
      (node (ref "U1") (pin "P6") (pinfunction "COMP_P6") (pintype "bidirectional"))
    )
    (net (code "38") (name "Net-(U1-IN+)") (class "Default")
      (node (ref "C1") (pin "2") (pinfunction "2_2") (pintype "passive"))
      (node (ref "R1") (pin "1") (pinfunction "1_1") (pintype "passive"))
      (node (ref "R2") (pin "1") (pinfunction "1_1") (pintype "passive"))
      (node (ref "U1") (pin "P4") (pinfunction "IN+_P4") (pintype "bidirectional"))
    )
    (net (code "39") (name "Net-(U1-IN-)") (class "Default")
      (node (ref "R55") (pin "1") (pinfunction "1_1") (pintype "passive"))
      (node (ref "U1") (pin "P5") (pinfunction "IN-_P5") (pintype "bidirectional"))
      (node (ref "VR1") (pin "1") (pinfunction "A_1") (pintype "passive"))
    )
    (net (code "40") (name "Net-(U1-MUTE)") (class "Default")
      (node (ref "C6") (pin "+") (pinfunction "+_+") (pintype "passive"))
      (node (ref "R52") (pin "2") (pinfunction "2_2") (pintype "passive"))
      (node (ref "U1") (pin "P2") (pinfunction "MUTE_P2") (pintype "bidirectional"))
    )
    (net (code "41") (name "Net-(U1-NOUT)") (class "Default")
      (node (ref "R48") (pin "2") (pinfunction "2_2") (pintype "passive"))
      (node (ref "U1") (pin "P14") (pinfunction "NOUT_P14") (pintype "bidirectional"))
    )
    (net (code "42") (name "Net-(U1-POUT)") (class "Default")
      (node (ref "R47") (pin "2") (pinfunction "2_2") (pintype "passive"))
      (node (ref "U1") (pin "P13") (pinfunction "POUT_P13") (pintype "bidirectional"))
    )
    (net (code "43") (name "Net-(U2-BIASP)") (class "Default")
      (node (ref "C20") (pin "2") (pinfunction "2_2") (pintype "passive"))
      (node (ref "R3") (pin "2") (pinfunction "2_2") (pintype "passive"))
      (node (ref "U2") (pin "P12") (pinfunction "BIASP_P12") (pintype "bidirectional"))
    )
    (net (code "44") (name "Net-(U2-COMP)") (class "Default")
      (node (ref "C22") (pin "2") (pinfunction "2_2") (pintype "passive"))
      (node (ref "U2") (pin "P6") (pinfunction "COMP_P6") (pintype "bidirectional"))
    )
    (net (code "45") (name "Net-(U2-IN+)") (class "Default")
      (node (ref "C29") (pin "2") (pinfunction "2_2") (pintype "passive"))
      (node (ref "R10") (pin "1") (pinfunction "1_1") (pintype "passive"))
      (node (ref "R11") (pin "1") (pinfunction "1_1") (pintype "passive"))
      (node (ref "U2") (pin "P4") (pinfunction "IN+_P4") (pintype "bidirectional"))
    )
    (net (code "46") (name "Net-(U2-IN-)") (class "Default")
      (node (ref "R12") (pin "1") (pinfunction "1_1") (pintype "passive"))
      (node (ref "U2") (pin "P5") (pinfunction "IN-_P5") (pintype "bidirectional"))
      (node (ref "VR3") (pin "1") (pinfunction "A_1") (pintype "passive"))
    )
    (net (code "47") (name "Net-(U2-MUTE)") (class "Default")
      (node (ref "C28") (pin "+") (pinfunction "+_+") (pintype "passive"))
      (node (ref "R9") (pin "2") (pinfunction "2_2") (pintype "passive"))
      (node (ref "U2") (pin "P2") (pinfunction "MUTE_P2") (pintype "bidirectional"))
    )
    (net (code "48") (name "Net-(U2-NOUT)") (class "Default")
      (node (ref "R7") (pin "2") (pinfunction "2_2") (pintype "passive"))
      (node (ref "U2") (pin "P14") (pinfunction "NOUT_P14") (pintype "bidirectional"))
    )
    (net (code "49") (name "Net-(U2-POUT)") (class "Default")
      (node (ref "R6") (pin "2") (pinfunction "2_2") (pintype "passive"))
      (node (ref "U2") (pin "P13") (pinfunction "POUT_P13") (pintype "bidirectional"))
    )
    (net (code "50") (name "Net-(U3-BIASP)") (class "Default")
      (node (ref "C35") (pin "2") (pinfunction "2_2") (pintype "passive"))
      (node (ref "R14") (pin "2") (pinfunction "2_2") (pintype "passive"))
      (node (ref "U3") (pin "P12") (pinfunction "BIASP_P12") (pintype "bidirectional"))
    )
    (net (code "51") (name "Net-(U3-COMP)") (class "Default")
      (node (ref "C37") (pin "2") (pinfunction "2_2") (pintype "passive"))
      (node (ref "U3") (pin "P6") (pinfunction "COMP_P6") (pintype "bidirectional"))
    )
    (net (code "52") (name "Net-(U3-IN+)") (class "Default")
      (node (ref "C44") (pin "2") (pinfunction "2_2") (pintype "passive"))
      (node (ref "R21") (pin "1") (pinfunction "1_1") (pintype "passive"))
      (node (ref "R22") (pin "1") (pinfunction "1_1") (pintype "passive"))
      (node (ref "U3") (pin "P4") (pinfunction "IN+_P4") (pintype "bidirectional"))
    )
    (net (code "53") (name "Net-(U3-IN-)") (class "Default")
      (node (ref "R23") (pin "1") (pinfunction "1_1") (pintype "passive"))
      (node (ref "U3") (pin "P5") (pinfunction "IN-_P5") (pintype "bidirectional"))
      (node (ref "VR5") (pin "1") (pinfunction "A_1") (pintype "passive"))
    )
    (net (code "54") (name "Net-(U3-MUTE)") (class "Default")
      (node (ref "C43") (pin "+") (pinfunction "+_+") (pintype "passive"))
      (node (ref "R20") (pin "2") (pinfunction "2_2") (pintype "passive"))
      (node (ref "U3") (pin "P2") (pinfunction "MUTE_P2") (pintype "bidirectional"))
    )
    (net (code "55") (name "Net-(U3-NOUT)") (class "Default")
      (node (ref "R18") (pin "2") (pinfunction "2_2") (pintype "passive"))
      (node (ref "U3") (pin "P14") (pinfunction "NOUT_P14") (pintype "bidirectional"))
    )
    (net (code "56") (name "Net-(U3-POUT)") (class "Default")
      (node (ref "R17") (pin "2") (pinfunction "2_2") (pintype "passive"))
      (node (ref "U3") (pin "P13") (pinfunction "POUT_P13") (pintype "bidirectional"))
    )
    (net (code "57") (name "Net-(VR1-B)") (class "Default")
      (node (ref "R56") (pin "2") (pinfunction "2_2") (pintype "passive"))
      (node (ref "VR1") (pin "2") (pinfunction "B_2") (pintype "passive"))
      (node (ref "VR1") (pin "3") (pinfunction "C_3") (pintype "passive"))
    )
    (net (code "58") (name "Net-(VR3-B)") (class "Default")
      (node (ref "R13") (pin "2") (pinfunction "2_2") (pintype "passive"))
      (node (ref "VR3") (pin "2") (pinfunction "B_2") (pintype "passive"))
      (node (ref "VR3") (pin "3") (pinfunction "C_3") (pintype "passive"))
    )
    (net (code "59") (name "Net-(VR5-B)") (class "Default")
      (node (ref "R24") (pin "2") (pinfunction "2_2") (pintype "passive"))
      (node (ref "VR5") (pin "2") (pinfunction "B_2") (pintype "passive"))
      (node (ref "VR5") (pin "3") (pinfunction "C_3") (pintype "passive"))
    )
    (net (code "60") (name "V+") (class "Default")
      (node (ref "C11") (pin "1") (pinfunction "1_1") (pintype "passive"))
      (node (ref "C12") (pin "+") (pinfunction "+_+") (pintype "passive"))
      (node (ref "C17") (pin "+") (pinfunction "+_+") (pintype "passive"))
      (node (ref "C19") (pin "1") (pinfunction "1_1") (pintype "passive"))
      (node (ref "C23") (pin "+") (pinfunction "+_+") (pintype "passive"))
      (node (ref "C25") (pin "1") (pinfunction "1_1") (pintype "passive"))
      (node (ref "C32") (pin "+") (pinfunction "+_+") (pintype "passive"))
      (node (ref "C34") (pin "1") (pinfunction "1_1") (pintype "passive"))
      (node (ref "C38") (pin "+") (pinfunction "+_+") (pintype "passive"))
      (node (ref "C4") (pin "+") (pinfunction "+_+") (pintype "passive"))
      (node (ref "C40") (pin "1") (pinfunction "1_1") (pintype "passive"))
      (node (ref "C5") (pin "1") (pinfunction "1_1") (pintype "passive"))
      (node (ref "J10") (pin "P$1") (pinfunction "1_P$1") (pintype "bidirectional"))
      (node (ref "J12") (pin "P$1") (pinfunction "1_P$1") (pintype "bidirectional"))
      (node (ref "J2") (pin "P$4") (pinfunction "4_P$4") (pintype "passive"))
      (node (ref "J6") (pin "P$1") (pinfunction "1_P$1") (pintype "bidirectional"))
      (node (ref "U1") (pin "P15") (pinfunction "+VCC_P15") (pintype "passive"))
      (node (ref "U2") (pin "P15") (pinfunction "+VCC_P15") (pintype "passive"))
      (node (ref "U3") (pin "P15") (pinfunction "+VCC_P15") (pintype "passive"))
    )
    (net (code "61") (name "V-") (class "Default")
      (node (ref "C13") (pin "2") (pinfunction "2_2") (pintype "passive"))
      (node (ref "C14") (pin "-") (pinfunction "-_-") (pintype "passive"))
      (node (ref "C16") (pin "-") (pinfunction "-_-") (pintype "passive"))
      (node (ref "C18") (pin "2") (pinfunction "2_2") (pintype "passive"))
      (node (ref "C2") (pin "-") (pinfunction "-_-") (pintype "passive"))
      (node (ref "C24") (pin "-") (pinfunction "-_-") (pintype "passive"))
      (node (ref "C26") (pin "2") (pinfunction "2_2") (pintype "passive"))
      (node (ref "C3") (pin "2") (pinfunction "2_2") (pintype "passive"))
      (node (ref "C31") (pin "-") (pinfunction "-_-") (pintype "passive"))
      (node (ref "C33") (pin "2") (pinfunction "2_2") (pintype "passive"))
      (node (ref "C39") (pin "-") (pinfunction "-_-") (pintype "passive"))
      (node (ref "C41") (pin "2") (pinfunction "2_2") (pintype "passive"))
      (node (ref "J13") (pin "P$3") (pinfunction "3_P$3") (pintype "bidirectional"))
      (node (ref "J2") (pin "P$3") (pinfunction "3_P$3") (pintype "passive"))
      (node (ref "J8") (pin "P$3") (pinfunction "3_P$3") (pintype "bidirectional"))
      (node (ref "J9") (pin "P$3") (pinfunction "3_P$3") (pintype "bidirectional"))
      (node (ref "U1") (pin "P10") (pinfunction "-VEE_P10") (pintype "power_in"))
      (node (ref "U2") (pin "P10") (pinfunction "-VEE_P10") (pintype "power_in"))
      (node (ref "U3") (pin "P10") (pinfunction "-VEE_P10") (pintype "power_in"))
    )
  )
)
